# ms_subsystem.net
KiCad netlist of a schematic drawn in EAGLE
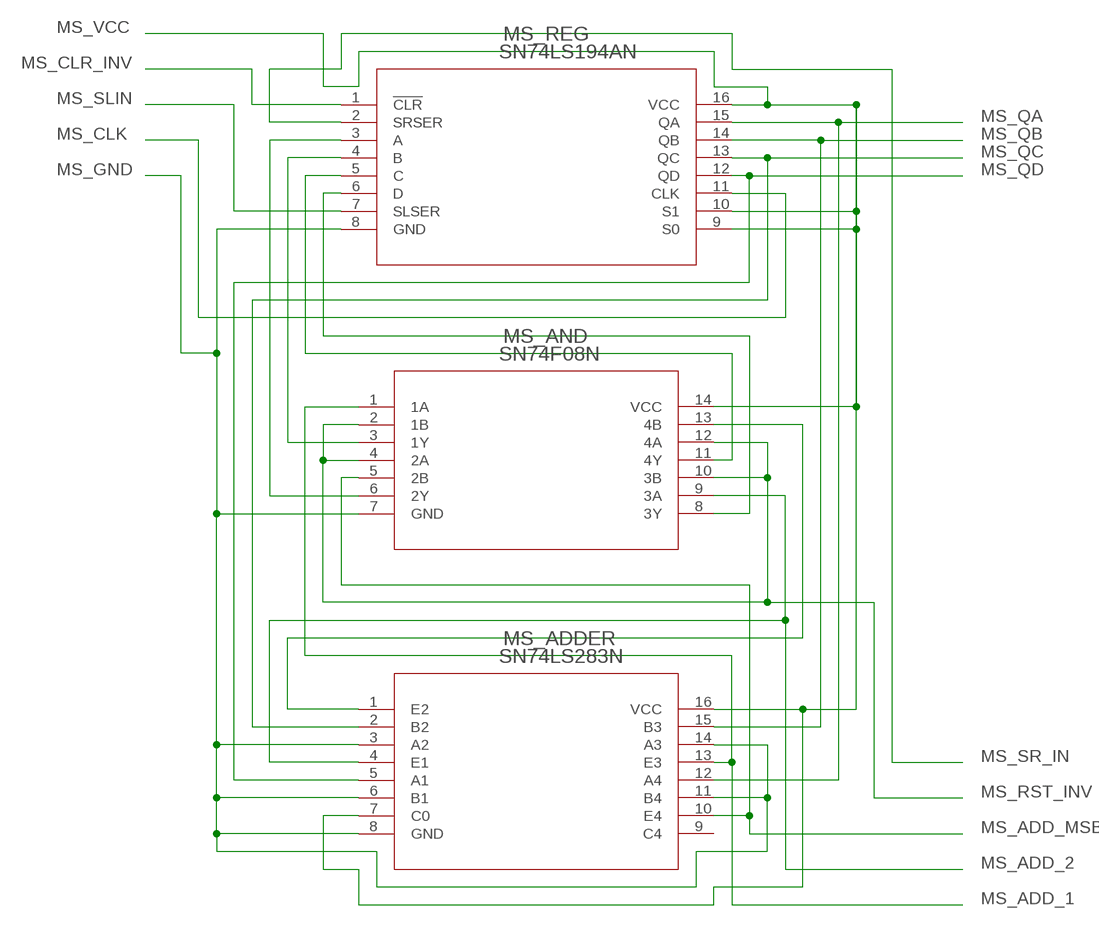
[diagram p0: schematic, sheet 1]

(export (version "E")
  (design (tool "Eeschema 10.0.6"))
  (components
    (comp (ref "MS_ADDER")
      (value "SN74LS283N")
      (footprint "eagle-import:N16")
      (fields
        (field (name "GENERIC_PART_NUMBER") "SN74LS283")
        (field (name "MANUFACTURER") "Texas Instruments")
      )
      (libsource (lib "eagle-import") (part "SN74LS283N"))
    )
    (comp (ref "MS_AND")
      (value "SN74F08N")
      (footprint "eagle-import:N14")
      (fields
        (field (name "GENERIC_PART_NUMBER") "SN74F08")
        (field (name "MANUFACTURER") "Texas Instruments")
      )
      (libsource (lib "eagle-import") (part "SN74F08N"))
    )
    (comp (ref "MS_REG")
      (value "SN74LS194AN")
      (footprint "eagle-import:N16")
      (fields
        (field (name "GENERIC_PART_NUMBER") "SN74LS194A")
        (field (name "MANUFACTURER") "Texas Instruments")
      )
      (libsource (lib "eagle-import") (part "SN74LS194AN"))
    )
  )
  (nets
    (net (code "1") (name "/MS_ADD_1") (class "Default")
      (node (ref "MS_ADDER") (pin "13") (pinfunction "E3_13") (pintype "output"))
      (node (ref "MS_AND") (pin "1") (pinfunction "1A_1") (pintype "input"))
    )
    (net (code "2") (name "/MS_ADD_2") (class "Default")
      (node (ref "MS_ADDER") (pin "4") (pinfunction "E1_4") (pintype "output"))
      (node (ref "MS_AND") (pin "9") (pinfunction "3A_9") (pintype "input"))
    )
    (net (code "3") (name "/MS_ADD_MSB") (class "Default")
      (node (ref "MS_ADDER") (pin "10") (pinfunction "E4_10") (pintype "output"))
      (node (ref "MS_AND") (pin "5") (pinfunction "2B_5") (pintype "input"))
    )
    (net (code "4") (name "/MS_CLK") (class "Default")
      (node (ref "MS_REG") (pin "11") (pinfunction "CLK_11") (pintype "input"))
    )
    (net (code "5") (name "/MS_CLR_INV") (class "Default")
      (node (ref "MS_REG") (pin "1") (pinfunction "~{CLR}_1") (pintype "input"))
    )
    (net (code "6") (name "/MS_GND") (class "Default")
      (node (ref "MS_ADDER") (pin "11") (pinfunction "B4_11") (pintype "input"))
      (node (ref "MS_ADDER") (pin "14") (pinfunction "A3_14") (pintype "input"))
      (node (ref "MS_ADDER") (pin "3") (pinfunction "A2_3") (pintype "input"))
      (node (ref "MS_ADDER") (pin "6") (pinfunction "B1_6") (pintype "input"))
      (node (ref "MS_ADDER") (pin "8") (pinfunction "GND_8") (pintype "power_in"))
      (node (ref "MS_AND") (pin "7") (pinfunction "GND_7") (pintype "power_in"))
      (node (ref "MS_REG") (pin "8") (pinfunction "GND_8") (pintype "power_in"))
    )
    (net (code "7") (name "/MS_QA") (class "Default")
      (node (ref "MS_ADDER") (pin "12") (pinfunction "A4_12") (pintype "input"))
      (node (ref "MS_REG") (pin "15") (pinfunction "QA_15") (pintype "output"))
    )
    (net (code "8") (name "/MS_QB") (class "Default")
      (node (ref "MS_ADDER") (pin "15") (pinfunction "B3_15") (pintype "input"))
      (node (ref "MS_REG") (pin "14") (pinfunction "QB_14") (pintype "output"))
    )
    (net (code "9") (name "/MS_QC") (class "Default")
      (node (ref "MS_ADDER") (pin "2") (pinfunction "B2_2") (pintype "input"))
      (node (ref "MS_REG") (pin "13") (pinfunction "QC_13") (pintype "output"))
    )
    (net (code "10") (name "/MS_QD") (class "Default")
      (node (ref "MS_ADDER") (pin "5") (pinfunction "A1_5") (pintype "input"))
      (node (ref "MS_REG") (pin "12") (pinfunction "QD_12") (pintype "output"))
    )
    (net (code "11") (name "/MS_RST_INV") (class "Default")
      (node (ref "MS_AND") (pin "10") (pinfunction "3B_10") (pintype "input"))
      (node (ref "MS_AND") (pin "12") (pinfunction "4A_12") (pintype "input"))
      (node (ref "MS_AND") (pin "2") (pinfunction "1B_2") (pintype "input"))
      (node (ref "MS_AND") (pin "4") (pinfunction "2A_4") (pintype "input"))
    )
    (net (code "12") (name "/MS_SLIN") (class "Default")
      (node (ref "MS_REG") (pin "7") (pinfunction "SLSER_7") (pintype "input"))
    )
    (net (code "13") (name "/MS_SR_IN") (class "Default")
      (node (ref "MS_REG") (pin "2") (pinfunction "SRSER_2") (pintype "input"))
    )
    (net (code "14") (name "/MS_VCC") (class "Default")
      (node (ref "MS_ADDER") (pin "16") (pinfunction "VCC_16") (pintype "power_in"))
      (node (ref "MS_ADDER") (pin "7") (pinfunction "C0_7") (pintype "input"))
      (node (ref "MS_AND") (pin "14") (pinfunction "VCC_14") (pintype "power_in"))
      (node (ref "MS_REG") (pin "10") (pinfunction "S1_10") (pintype "input"))
      (node (ref "MS_REG") (pin "16") (pinfunction "VCC_16") (pintype "power_in"))
      (node (ref "MS_REG") (pin "9") (pinfunction "S0_9") (pintype "input"))
    )
    (net (code "15") (name "Net-(MS_ADDER-E2)") (class "Default")
      (node (ref "MS_ADDER") (pin "1") (pinfunction "E2_1") (pintype "output"))
      (node (ref "MS_AND") (pin "13") (pinfunction "4B_13") (pintype "input"))
    )
    (net (code "16") (name "Net-(MS_AND-1Y)") (class "Default")
      (node (ref "MS_AND") (pin "3") (pinfunction "1Y_3") (pintype "output"))
      (node (ref "MS_REG") (pin "4") (pinfunction "B_4") (pintype "input"))
    )
    (net (code "17") (name "Net-(MS_AND-2Y)") (class "Default")
      (node (ref "MS_AND") (pin "6") (pinfunction "2Y_6") (pintype "output"))
      (node (ref "MS_REG") (pin "3") (pinfunction "A_3") (pintype "input"))
    )
    (net (code "18") (name "Net-(MS_AND-3Y)") (class "Default")
      (node (ref "MS_AND") (pin "8") (pinfunction "3Y_8") (pintype "output"))
      (node (ref "MS_REG") (pin "6") (pinfunction "D_6") (pintype "input"))
    )
    (net (code "19") (name "Net-(MS_AND-4Y)") (class "Default")
      (node (ref "MS_AND") (pin "11") (pinfunction "4Y_11") (pintype "output"))
      (node (ref "MS_REG") (pin "5") (pinfunction "C_5") (pintype "input"))
    )
    (net (code "20") (name "unconnected-(MS_ADDER-C4-Pad9)") (class "Default")
      (node (ref "MS_ADDER") (pin "9") (pinfunction "C4_9") (pintype "input"))
    )
  )
)
